# SCH_zazanfc_2026-02-07.net
KiCad netlist of a schematic drawn in EasyEDA
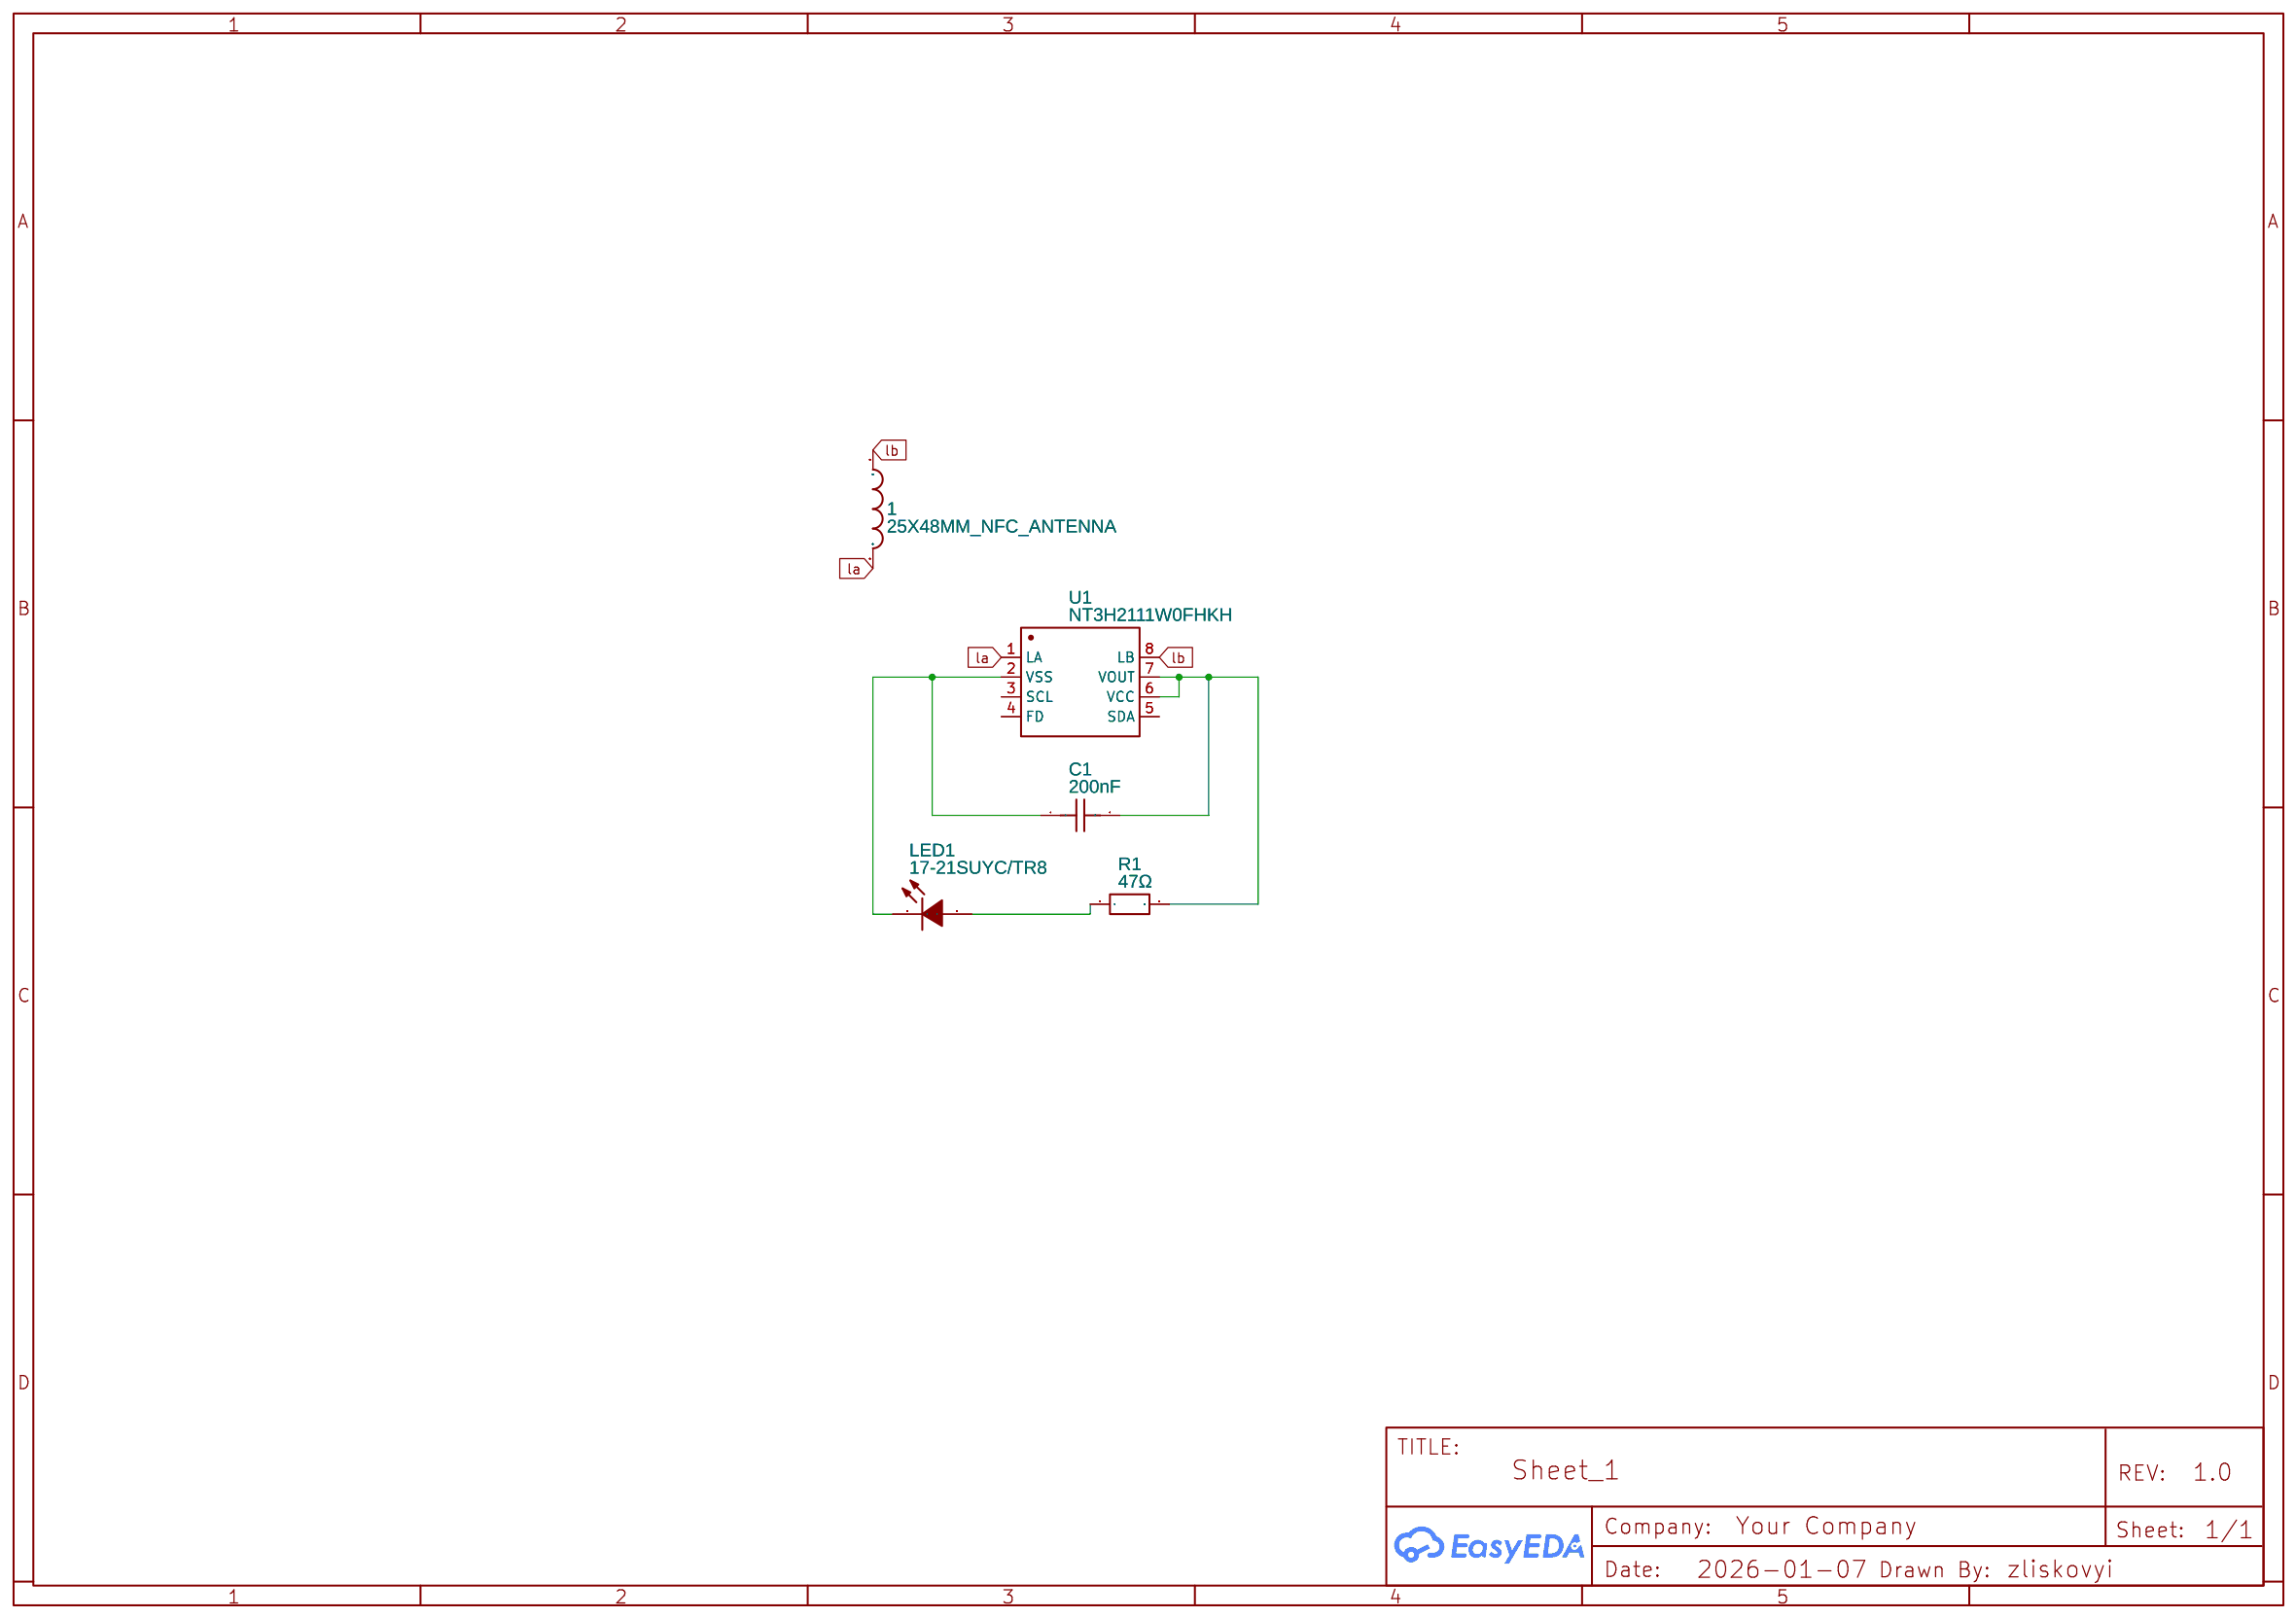
[diagram p0: schematic sheet]

(export (version "E")
  (design (tool "Eeschema 10.0.6"))
  (components
    (comp (ref "1") (value "25X48MM_NFC_ANTENNA") (libsource (lib "") (part "25X48MM_NFC_ANTENNA")))
    (comp (ref "C1") (value "200nF") (libsource (lib "") (part "C_0603_US")))
    (comp (ref "LED1")
      (value "17-21SUYC/TR8")
      (fields (field (name "Manufacturer Part") "KT-0805黄灯") (field (name "Manufacturer") "KENTO"))
      (libsource (lib "") (part "17-21SUYC/TR8"))
    )
    (comp (ref "R1") (value "47Ω") (libsource (lib "") (part "R_0603_EU")))
    (comp (ref "U1")
      (value "NT3H2111W0FHKH")
      (fields (field (name "Manufacturer") "NXP(恩智浦)"))
      (libsource (lib "") (part "NT3H2111W0FHKH"))
    )
  )
  (nets
    (net (code "1") (name "Net-(LED1-+)") (class "Default")
      (node (ref "LED1") (pin "1") (pinfunction "+_1") (pintype "unspecified"))
      (node (ref "R1") (pin "1") (pinfunction "1_1") (pintype "unspecified"))
    )
    (net (code "2") (name "Net-(LED1--)") (class "Default")
      (node (ref "C1") (pin "1") (pinfunction "1_1") (pintype "unspecified"))
      (node (ref "LED1") (pin "2") (pinfunction "-_2") (pintype "unspecified"))
      (node (ref "U1") (pin "2") (pinfunction "VSS_2") (pintype "unspecified"))
    )
    (net (code "3") (name "Net-(U1-VCC)") (class "Default")
      (node (ref "C1") (pin "2") (pinfunction "2_2") (pintype "unspecified"))
      (node (ref "R1") (pin "2") (pinfunction "2_2") (pintype "unspecified"))
      (node (ref "U1") (pin "6") (pinfunction "VCC_6") (pintype "unspecified"))
      (node (ref "U1") (pin "7") (pinfunction "VOUT_7") (pintype "unspecified"))
    )
    (net (code "4") (name "la") (class "Default")
      (node (ref "1") (pin "P$2") (pinfunction "P$2_P$2") (pintype "bidirectional"))
      (node (ref "U1") (pin "1") (pinfunction "LA_1") (pintype "unspecified"))
    )
    (net (code "5") (name "lb") (class "Default")
      (node (ref "1") (pin "P$1") (pinfunction "P$1_P$1") (pintype "bidirectional"))
      (node (ref "U1") (pin "8") (pinfunction "LB_8") (pintype "unspecified"))
    )
    (net (code "6") (name "unconnected-(U1-FD-Pad4)") (class "Default")
      (node (ref "U1") (pin "4") (pinfunction "FD_4") (pintype "unspecified"))
    )
    (net (code "7") (name "unconnected-(U1-SCL-Pad3)") (class "Default")
      (node (ref "U1") (pin "3") (pinfunction "SCL_3") (pintype "unspecified"))
    )
    (net (code "8") (name "unconnected-(U1-SDA-Pad5)") (class "Default")
      (node (ref "U1") (pin "5") (pinfunction "SDA_5") (pintype "unspecified"))
    )
  )
)
